# sedsna.net
KiCad netlist of a schematic drawn in Altium Designer
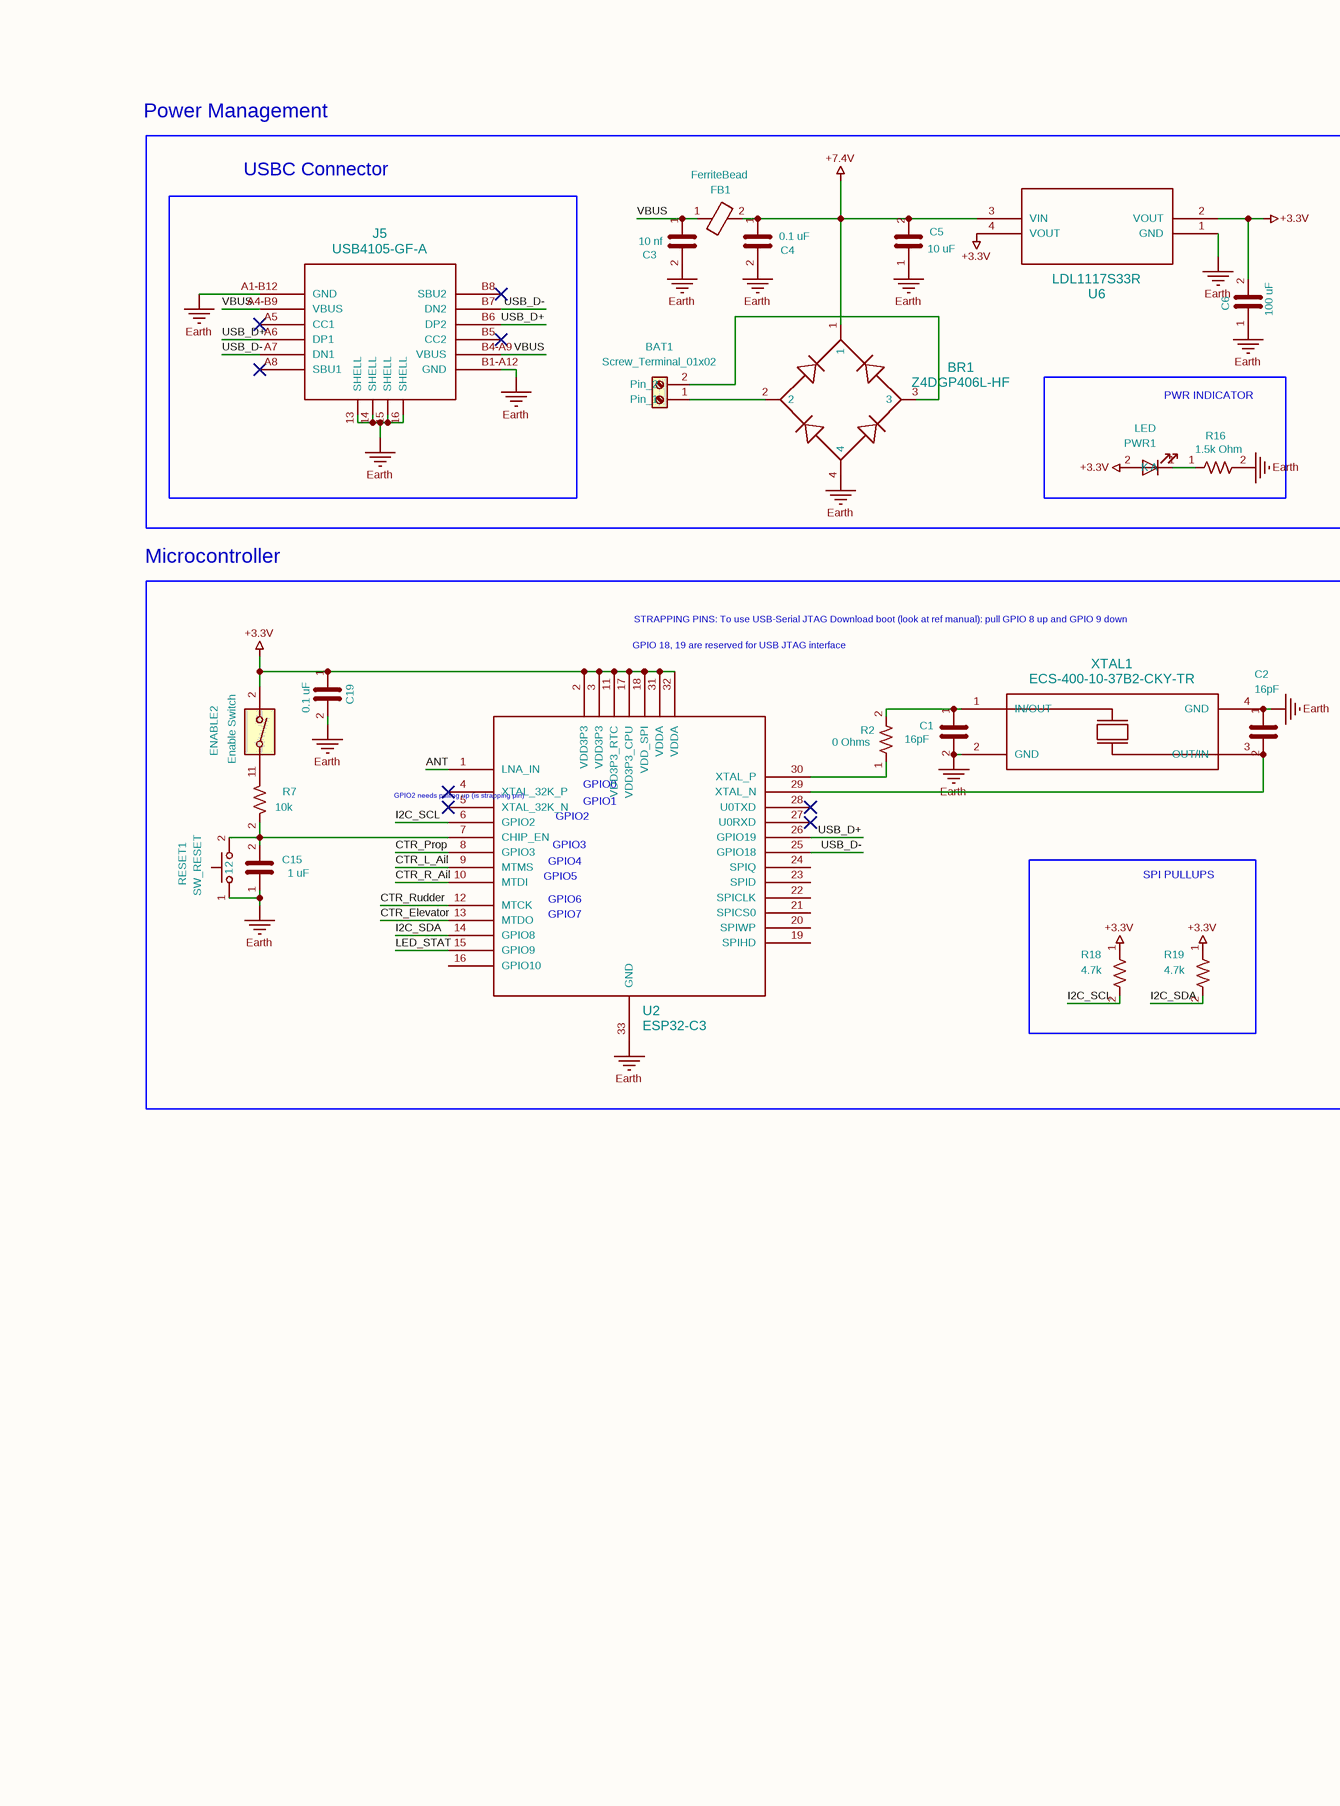
[diagram p0: sedsna.SchDoc, left]
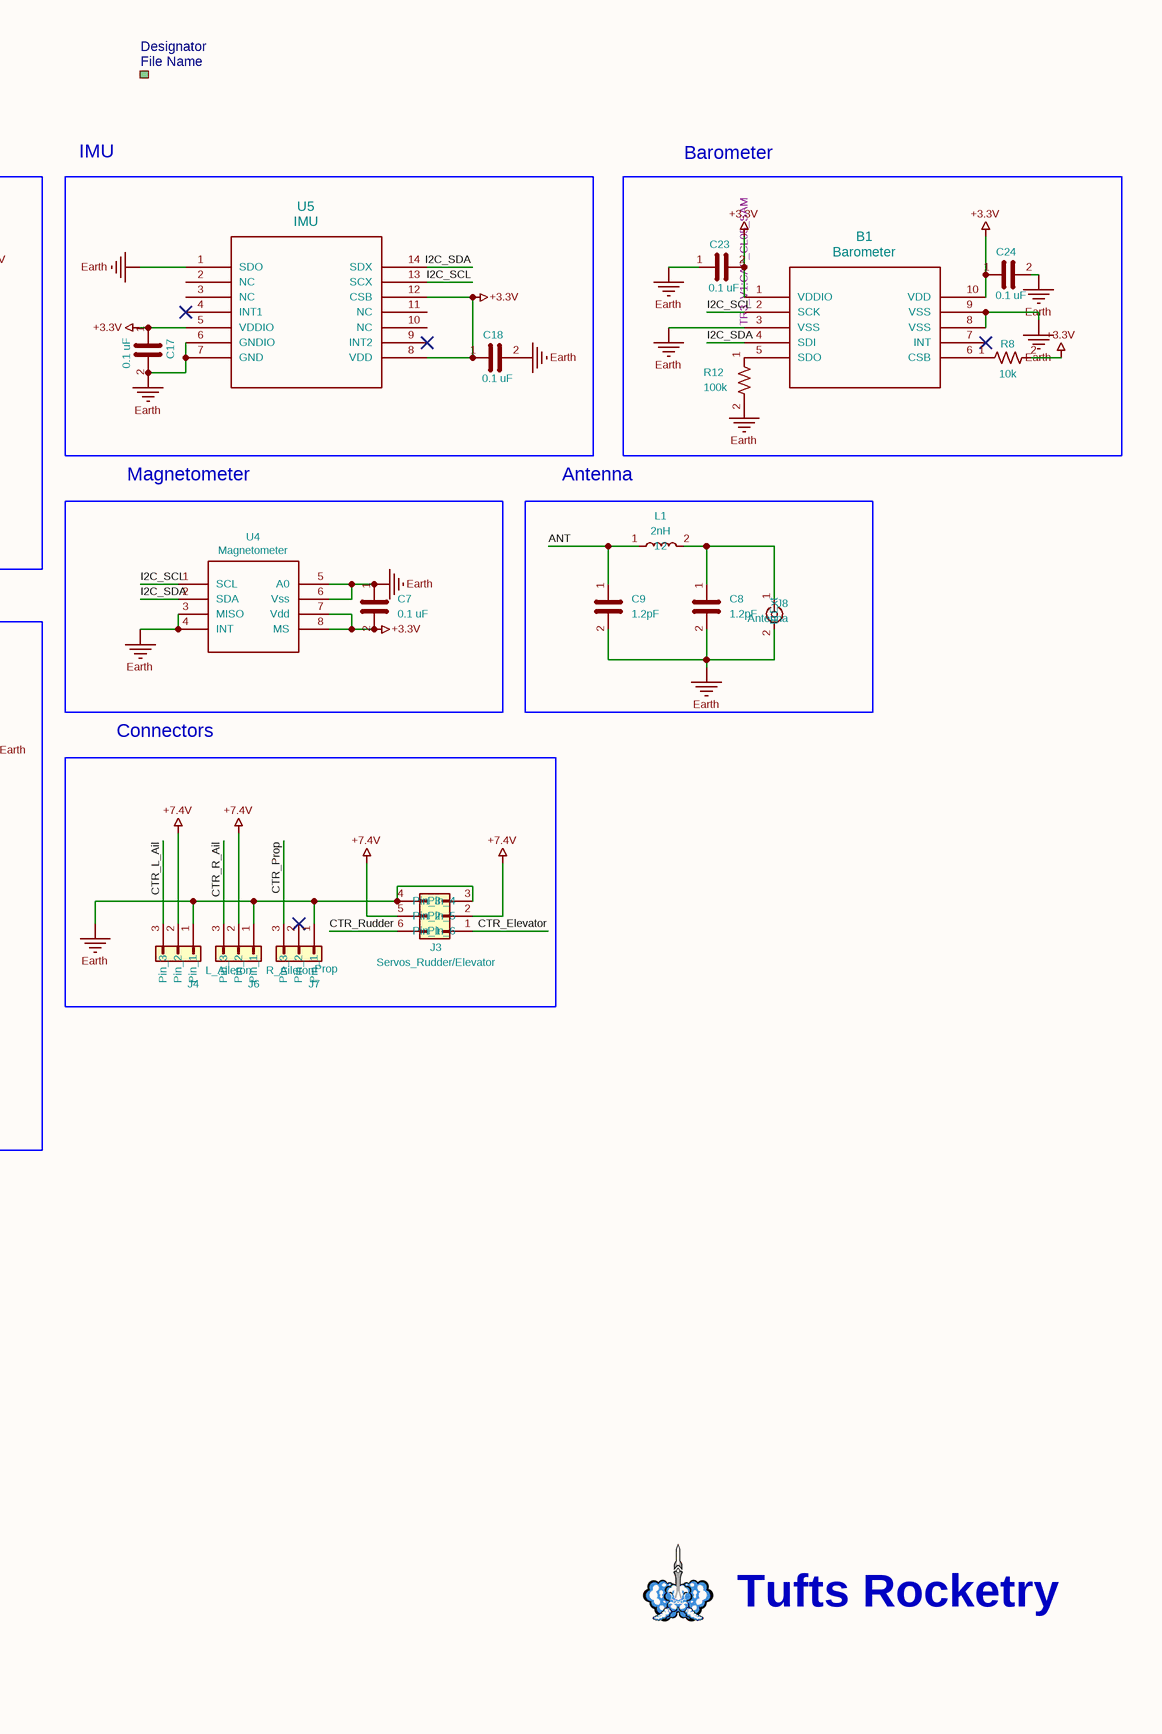
[diagram p1: sedsna.SchDoc, right]

(export (version "E")
  (design (tool "Eeschema 10.0.6"))
  (components
    (comp (ref "B1")
      (value "Barometer")
      (footprint "QFN10_BMP581_BOS")
      (libsource (lib "TR3_V1") (part "BMP581"))
    )
    (comp (ref "BAT1")
      (value "Screw_Terminal_01x02")
      (footprint "TerminalBlock_bornier-2_P5.08mm")
      (libsource (lib "TR3_V1") (part "Screw_Terminal_01x02"))
    )
    (comp (ref "BR1")
      (value "Z4DGP406L-HF")
      (footprint "Z4DGP406L-HF_footprint_N")
      (libsource (lib "TR3_V1") (part "Z4DGP406L-HF"))
    )
    (comp (ref "C1") (value "16pF") (libsource (lib "Device") (part "C")))
    (comp (ref "C2") (value "16pF") (libsource (lib "Device") (part "C")))
    (comp (ref "C3") (value "10 nf") (footprint "C_0603_1608Metric") (libsource (lib "TR3_V1") (part "C")))
    (comp (ref "C4") (value "0.1 uF") (footprint "CAP_CL05_SAM") (libsource (lib "TR3_V1") (part "C")))
    (comp (ref "C5") (value "10 uF") (footprint "C_0805_2012Metric") (libsource (lib "TR3_V1") (part "C")))
    (comp (ref "C6") (value "100 uF") (footprint "C_1206_3216Metric") (libsource (lib "TR3_V1") (part "C")))
    (comp (ref "C7") (value "0.1 uF") (libsource (lib "Device") (part "C")))
    (comp (ref "C8") (value "1.2pF") (libsource (lib "Device") (part "C")))
    (comp (ref "C9") (value "1.2pF") (libsource (lib "Device") (part "C")))
    (comp (ref "C15") (value "1 uF") (footprint "C_0603_1608Metric") (libsource (lib "TR3_V1") (part "C")))
    (comp (ref "C17") (value "0.1 uF") (footprint "CAP_CL05_SAM") (libsource (lib "TR3_V1") (part "C")))
    (comp (ref "C18") (value "0.1 uF") (footprint "CAP_CL05_SAM") (libsource (lib "TR3_V1") (part "C")))
    (comp (ref "C19") (value "0.1 uF") (footprint "CAP_CL05_SAM") (libsource (lib "TR3_V1") (part "C")))
    (comp (ref "C23")
      (value "0.1 uF")
      (footprint "TR3_V1:CAP_CL05_SAM")
      (libsource (lib "TR3_V1") (part "C"))
    )
    (comp (ref "C24") (value "0.1 uF") (footprint "CAP_CL05_SAM") (libsource (lib "TR3_V1") (part "C")))
    (comp (ref "ENABLE2")
      (value "Enable Switch")
      (footprint "SW_DS04-254-2-01BK-SMT")
      (libsource (lib "TR3_V1") (part "SW_DIP_x01"))
    )
    (comp (ref "FB1")
      (value "FerriteBead")
      (footprint "FB_MI0805K400R-10")
      (libsource (lib "Device") (part "FerriteBead"))
    )
    (comp (ref "J3")
      (value "Servos_Rudder/Elevator")
      (libsource (lib "Connector_Generic") (part "Conn_02x03_Counter_Clockwise"))
    )
    (comp (ref "J4") (value "L_Aileron") (libsource (lib "Connector_Generic") (part "Conn_01x03")))
    (comp (ref "J5")
      (value "USB4105-GF-A")
      (footprint "USB4105_GCT")
      (libsource (lib "TR3_V1") (part "USB4105-GF-A"))
    )
    (comp (ref "J6") (value "R_Aileron") (libsource (lib "Connector_Generic") (part "Conn_01x03")))
    (comp (ref "J7") (value "Prop") (libsource (lib "Connector_Generic") (part "Conn_01x03")))
    (comp (ref "J8") (value "Antenna") (libsource (lib "Connector") (part "Conn_Coaxial_Small")))
    (comp (ref "L1") (value "2nH") (libsource (lib "Device") (part "L")))
    (comp (ref "PWR1") (value "LED") (footprint "150080RS75000_WRE") (libsource (lib "TR3_V1") (part "LED")))
    (comp (ref "R2") (value "0 Ohms") (libsource (lib "Device") (part "R_US")))
    (comp (ref "R7")
      (value "10k")
      (footprint "R_0603_1608Metric_Pad0.98x0.95mm_HandSolder")
      (libsource (lib "TR3_V1") (part "R_US"))
    )
    (comp (ref "R8")
      (value "10k")
      (footprint "R_0603_1608Metric_Pad0.98x0.95mm_HandSolder")
      (libsource (lib "TR3_V1") (part "R_US"))
    )
    (comp (ref "R12")
      (value "100k")
      (footprint "R_0603_1608Metric_Pad0.98x0.95mm_HandSolder")
      (libsource (lib "TR3_V1") (part "R_US"))
    )
    (comp (ref "R16")
      (value "1.5k Ohm")
      (footprint "R_0603_1608Metric_Pad0.98x0.95mm_HandSolder")
      (libsource (lib "TR3_V1") (part "R_US"))
    )
    (comp (ref "R18")
      (value "4.7k")
      (footprint "R_0603_1608Metric_Pad0.98x0.95mm_HandSolder")
      (libsource (lib "Device") (part "R_US"))
    )
    (comp (ref "R19")
      (value "4.7k")
      (footprint "R_0603_1608Metric_Pad0.98x0.95mm_HandSolder")
      (libsource (lib "Device") (part "R_US"))
    )
    (comp (ref "RESET1")
      (value "SW_RESET")
      (footprint "2-pronged_THT_button")
      (libsource (lib "TR3_V1") (part "SW_Push"))
    )
    (comp (ref "U2")
      (value "ESP32-C3")
      (footprint "QFN32_5X5_EXP")
      (libsource (lib "sedsna") (part "ESP32-C3"))
    )
    (comp (ref "U4") (value "Magnetometer") (libsource (lib "TR3_V1_from_sun") (part "MAGNETO-MLX90395KDC")))
    (comp (ref "U5") (value "IMU") (footprint "BMI323_BOS") (libsource (lib "TR3_V1") (part "BMI323")))
    (comp (ref "U6")
      (value "LDL1117S33R")
      (footprint "SOT223_STM")
      (libsource (lib "TR3_V1") (part "LDL1117S33R"))
    )
    (comp (ref "XTAL1")
      (value "ECS-400-10-37B2-CKY-TR")
      (footprint "ECX-1637B2_ECS")
      (libsource (lib "TR3_V1") (part "ECS-400-10-37B2-CKY-TR"))
    )
  )
  (nets
    (net (code "1") (name "+3.3V") (class "Default")
      (node (ref "B1") (pin "1") (pinfunction "VDDIO_1") (pintype "passive"))
      (node (ref "B1") (pin "10") (pinfunction "VDD_10") (pintype "passive"))
      (node (ref "C17") (pin "1") (pinfunction "1_1") (pintype "passive"))
      (node (ref "C18") (pin "1") (pinfunction "1_1") (pintype "passive"))
      (node (ref "C19") (pin "1") (pinfunction "1_1") (pintype "passive"))
      (node (ref "C23") (pin "2") (pinfunction "2_2") (pintype "passive"))
      (node (ref "C24") (pin "1") (pinfunction "1_1") (pintype "passive"))
      (node (ref "C6") (pin "2") (pinfunction "2_2") (pintype "passive"))
      (node (ref "C7") (pin "2") (pinfunction "2_2") (pintype "passive"))
      (node (ref "ENABLE2") (pin "2") (pinfunction "2_2") (pintype "passive"))
      (node (ref "PWR1") (pin "2") (pinfunction "A_2") (pintype "passive"))
      (node (ref "R18") (pin "1") (pinfunction "1_1") (pintype "passive"))
      (node (ref "R19") (pin "1") (pinfunction "1_1") (pintype "passive"))
      (node (ref "R8") (pin "2") (pinfunction "2_2") (pintype "passive"))
      (node (ref "U2") (pin "11") (pinfunction "VDD3P3_RTC_11") (pintype "passive"))
      (node (ref "U2") (pin "17") (pinfunction "VDD3P3_CPU_17") (pintype "passive"))
      (node (ref "U2") (pin "18") (pinfunction "VDD_SPI_18") (pintype "passive"))
      (node (ref "U2") (pin "2") (pinfunction "VDD3P3_2") (pintype "passive"))
      (node (ref "U2") (pin "3") (pinfunction "VDD3P3_3") (pintype "passive"))
      (node (ref "U2") (pin "31") (pinfunction "VDDA_31") (pintype "passive"))
      (node (ref "U2") (pin "32") (pinfunction "VDDA_32") (pintype "passive"))
      (node (ref "U4") (pin "7") (pinfunction "Vdd_7") (pintype "passive"))
      (node (ref "U4") (pin "8") (pinfunction "MS_8") (pintype "passive"))
      (node (ref "U5") (pin "12") (pinfunction "CSB_12") (pintype "passive"))
      (node (ref "U5") (pin "5") (pinfunction "VDDIO_5") (pintype "passive"))
      (node (ref "U5") (pin "8") (pinfunction "VDD_8") (pintype "passive"))
      (node (ref "U6") (pin "2") (pinfunction "VOUT_2") (pintype "passive"))
      (node (ref "U6") (pin "4") (pinfunction "VOUT_4") (pintype "passive"))
    )
    (net (code "2") (name "+7.4V") (class "Default")
      (node (ref "BR1") (pin "1") (pinfunction "1_1") (pintype "passive"))
      (node (ref "C4") (pin "1") (pinfunction "1_1") (pintype "passive"))
      (node (ref "C5") (pin "2") (pinfunction "2_2") (pintype "passive"))
      (node (ref "FB1") (pin "2") (pinfunction "2_2") (pintype "passive"))
      (node (ref "J3") (pin "2") (pinfunction "Pin_2_2") (pintype "passive"))
      (node (ref "J3") (pin "5") (pinfunction "Pin_5_5") (pintype "passive"))
      (node (ref "J4") (pin "2") (pinfunction "Pin_2_2") (pintype "passive"))
      (node (ref "J6") (pin "2") (pinfunction "Pin_2_2") (pintype "passive"))
      (node (ref "U6") (pin "3") (pinfunction "VIN_3") (pintype "passive"))
    )
    (net (code "3") (name "/ANT") (class "Default")
      (node (ref "C9") (pin "1") (pinfunction "1_1") (pintype "passive"))
      (node (ref "L1") (pin "1") (pinfunction "1_1") (pintype "passive"))
      (node (ref "U2") (pin "1") (pinfunction "LNA_IN_1") (pintype "passive"))
    )
    (net (code "4") (name "/CTR_Elevator") (class "Default")
      (node (ref "J3") (pin "1") (pinfunction "Pin_1_1") (pintype "passive"))
      (node (ref "U2") (pin "13") (pinfunction "MTDO_13") (pintype "passive"))
    )
    (net (code "5") (name "/CTR_L_Ail") (class "Default")
      (node (ref "J4") (pin "3") (pinfunction "Pin_3_3") (pintype "passive"))
      (node (ref "U2") (pin "9") (pinfunction "MTMS_9") (pintype "passive"))
    )
    (net (code "6") (name "/CTR_Prop") (class "Default")
      (node (ref "J7") (pin "3") (pinfunction "Pin_3_3") (pintype "passive"))
      (node (ref "U2") (pin "8") (pinfunction "GPIO3_8") (pintype "passive"))
    )
    (net (code "7") (name "/CTR_R_Ail") (class "Default")
      (node (ref "J6") (pin "3") (pinfunction "Pin_3_3") (pintype "passive"))
      (node (ref "U2") (pin "10") (pinfunction "MTDI_10") (pintype "passive"))
    )
    (net (code "8") (name "/CTR_Rudder") (class "Default")
      (node (ref "J3") (pin "6") (pinfunction "Pin_6_6") (pintype "passive"))
      (node (ref "U2") (pin "12") (pinfunction "MTCK_12") (pintype "passive"))
    )
    (net (code "9") (name "/I2C_SCL") (class "Default")
      (node (ref "B1") (pin "2") (pinfunction "SCK_2") (pintype "passive"))
      (node (ref "R18") (pin "2") (pinfunction "2_2") (pintype "passive"))
      (node (ref "U2") (pin "6") (pinfunction "GPIO2_6") (pintype "passive"))
      (node (ref "U4") (pin "1") (pinfunction "SCL_1") (pintype "passive"))
      (node (ref "U5") (pin "13") (pinfunction "SCX_13") (pintype "passive"))
    )
    (net (code "10") (name "/I2C_SDA") (class "Default")
      (node (ref "B1") (pin "4") (pinfunction "SDI_4") (pintype "passive"))
      (node (ref "R19") (pin "2") (pinfunction "2_2") (pintype "passive"))
      (node (ref "U2") (pin "14") (pinfunction "GPIO8_14") (pintype "passive"))
      (node (ref "U4") (pin "2") (pinfunction "SDA_2") (pintype "passive"))
      (node (ref "U5") (pin "14") (pinfunction "SDX_14") (pintype "passive"))
    )
    (net (code "11") (name "/LED_STAT") (class "Default")
      (node (ref "U2") (pin "15") (pinfunction "GPIO9_15") (pintype "passive"))
    )
    (net (code "12") (name "/USB_D+") (class "Default")
      (node (ref "J5") (pin "A6") (pinfunction "DP1_A6") (pintype "passive"))
      (node (ref "J5") (pin "B6") (pinfunction "DP2_B6") (pintype "passive"))
      (node (ref "U2") (pin "26") (pinfunction "GPIO19_26") (pintype "passive"))
    )
    (net (code "13") (name "/USB_D-") (class "Default")
      (node (ref "J5") (pin "A7") (pinfunction "DN1_A7") (pintype "passive"))
      (node (ref "J5") (pin "B7") (pinfunction "DN2_B7") (pintype "passive"))
      (node (ref "U2") (pin "25") (pinfunction "GPIO18_25") (pintype "passive"))
    )
    (net (code "14") (name "/VBUS") (class "Default")
      (node (ref "C3") (pin "1") (pinfunction "1_1") (pintype "passive"))
      (node (ref "FB1") (pin "1") (pinfunction "1_1") (pintype "passive"))
      (node (ref "J5") (pin "A4-B9") (pinfunction "VBUS_A4-B9") (pintype "passive"))
      (node (ref "J5") (pin "B4-A9") (pinfunction "VBUS_B4-A9") (pintype "passive"))
    )
    (net (code "15") (name "Earth") (class "Default")
      (node (ref "B1") (pin "3") (pinfunction "VSS_3") (pintype "passive"))
      (node (ref "B1") (pin "8") (pinfunction "VSS_8") (pintype "passive"))
      (node (ref "B1") (pin "9") (pinfunction "VSS_9") (pintype "passive"))
      (node (ref "BR1") (pin "4") (pinfunction "4_4") (pintype "passive"))
      (node (ref "C1") (pin "2") (pinfunction "2_2") (pintype "passive"))
      (node (ref "C15") (pin "1") (pinfunction "1_1") (pintype "passive"))
      (node (ref "C17") (pin "2") (pinfunction "2_2") (pintype "passive"))
      (node (ref "C18") (pin "2") (pinfunction "2_2") (pintype "passive"))
      (node (ref "C19") (pin "2") (pinfunction "2_2") (pintype "passive"))
      (node (ref "C2") (pin "1") (pinfunction "1_1") (pintype "passive"))
      (node (ref "C23") (pin "1") (pinfunction "1_1") (pintype "passive"))
      (node (ref "C24") (pin "2") (pinfunction "2_2") (pintype "passive"))
      (node (ref "C3") (pin "2") (pinfunction "2_2") (pintype "passive"))
      (node (ref "C4") (pin "2") (pinfunction "2_2") (pintype "passive"))
      (node (ref "C5") (pin "1") (pinfunction "1_1") (pintype "passive"))
      (node (ref "C6") (pin "1") (pinfunction "1_1") (pintype "passive"))
      (node (ref "C7") (pin "1") (pinfunction "1_1") (pintype "passive"))
      (node (ref "C8") (pin "2") (pinfunction "2_2") (pintype "passive"))
      (node (ref "C9") (pin "2") (pinfunction "2_2") (pintype "passive"))
      (node (ref "J3") (pin "3") (pinfunction "Pin_3_3") (pintype "passive"))
      (node (ref "J3") (pin "4") (pinfunction "Pin_4_4") (pintype "passive"))
      (node (ref "J4") (pin "1") (pinfunction "Pin_1_1") (pintype "passive"))
      (node (ref "J5") (pin "13") (pinfunction "SHELL_13") (pintype "passive"))
      (node (ref "J5") (pin "14") (pinfunction "SHELL_14") (pintype "passive"))
      (node (ref "J5") (pin "15") (pinfunction "SHELL_15") (pintype "passive"))
      (node (ref "J5") (pin "16") (pinfunction "SHELL_16") (pintype "passive"))
      (node (ref "J5") (pin "A1-B12") (pinfunction "GND_A1-B12") (pintype "passive"))
      (node (ref "J5") (pin "B1-A12") (pinfunction "GND_B1-A12") (pintype "passive"))
      (node (ref "J6") (pin "1") (pinfunction "Pin_1_1") (pintype "passive"))
      (node (ref "J7") (pin "1") (pinfunction "Pin_1_1") (pintype "passive"))
      (node (ref "J8") (pin "2") (pinfunction "Ext_2") (pintype "passive"))
      (node (ref "R12") (pin "2") (pinfunction "2_2") (pintype "passive"))
      (node (ref "R16") (pin "2") (pinfunction "2_2") (pintype "passive"))
      (node (ref "RESET1") (pin "1") (pinfunction "1_1") (pintype "passive"))
      (node (ref "U2") (pin "33") (pinfunction "GND_33") (pintype "passive"))
      (node (ref "U4") (pin "3") (pinfunction "MISO_3") (pintype "passive"))
      (node (ref "U4") (pin "4") (pinfunction "INT_4") (pintype "passive"))
      (node (ref "U4") (pin "5") (pinfunction "A0_5") (pintype "passive"))
      (node (ref "U4") (pin "6") (pinfunction "Vss_6") (pintype "passive"))
      (node (ref "U5") (pin "1") (pinfunction "SDO_1") (pintype "passive"))
      (node (ref "U5") (pin "6") (pinfunction "GNDIO_6") (pintype "passive"))
      (node (ref "U5") (pin "7") (pinfunction "GND_7") (pintype "passive"))
      (node (ref "U6") (pin "1") (pinfunction "GND_1") (pintype "passive"))
      (node (ref "XTAL1") (pin "2") (pinfunction "GND_2") (pintype "passive"))
      (node (ref "XTAL1") (pin "4") (pinfunction "GND_4") (pintype "passive"))
    )
    (net (code "16") (name "Net-(B1-CSB)") (class "Default")
      (node (ref "B1") (pin "6") (pinfunction "CSB_6") (pintype "passive"))
      (node (ref "R8") (pin "1") (pinfunction "1_1") (pintype "passive"))
    )
    (net (code "17") (name "Net-(B1-SDO)") (class "Default")
      (node (ref "B1") (pin "5") (pinfunction "SDO_5") (pintype "passive"))
      (node (ref "R12") (pin "1") (pinfunction "1_1") (pintype "passive"))
    )
    (net (code "18") (name "Net-(BAT1-Pin_1)") (class "Default")
      (node (ref "BAT1") (pin "1") (pinfunction "Pin_1_1") (pintype "passive"))
      (node (ref "BR1") (pin "2") (pinfunction "2_2") (pintype "passive"))
    )
    (net (code "19") (name "Net-(BAT1-Pin_2)") (class "Default")
      (node (ref "BAT1") (pin "2") (pinfunction "Pin_2_2") (pintype "passive"))
      (node (ref "BR1") (pin "3") (pinfunction "3_3") (pintype "passive"))
    )
    (net (code "20") (name "Net-(ENABLE2-Pad1)") (class "Default")
      (node (ref "ENABLE2") (pin "1") (pinfunction "1_1") (pintype "passive"))
      (node (ref "R7") (pin "1") (pinfunction "1_1") (pintype "passive"))
    )
    (net (code "21") (name "Net-(J8-In)") (class "Default")
      (node (ref "C8") (pin "1") (pinfunction "1_1") (pintype "passive"))
      (node (ref "J8") (pin "1") (pinfunction "In_1") (pintype "passive"))
      (node (ref "L1") (pin "2") (pinfunction "2_2") (pintype "passive"))
    )
    (net (code "22") (name "Net-(PWR1-K)") (class "Default")
      (node (ref "PWR1") (pin "1") (pinfunction "K_1") (pintype "passive"))
      (node (ref "R16") (pin "1") (pinfunction "1_1") (pintype "passive"))
    )
    (net (code "23") (name "Net-(U2-CHIP_EN)") (class "Default")
      (node (ref "C15") (pin "2") (pinfunction "2_2") (pintype "passive"))
      (node (ref "R7") (pin "2") (pinfunction "2_2") (pintype "passive"))
      (node (ref "RESET1") (pin "2") (pinfunction "2_2") (pintype "passive"))
      (node (ref "U2") (pin "7") (pinfunction "CHIP_EN_7") (pintype "passive"))
    )
    (net (code "24") (name "Net-(U2-XTAL_N)") (class "Default")
      (node (ref "C2") (pin "2") (pinfunction "2_2") (pintype "passive"))
      (node (ref "U2") (pin "29") (pinfunction "XTAL_N_29") (pintype "passive"))
      (node (ref "XTAL1") (pin "3") (pinfunction "OUT/IN_3") (pintype "passive"))
    )
    (net (code "25") (name "Net-(U2-XTAL_P)") (class "Default")
      (node (ref "R2") (pin "1") (pinfunction "1_1") (pintype "passive"))
      (node (ref "U2") (pin "30") (pinfunction "XTAL_P_30") (pintype "passive"))
    )
    (net (code "26") (name "Net-(XTAL1-IN{slash}OUT)") (class "Default")
      (node (ref "C1") (pin "1") (pinfunction "1_1") (pintype "passive"))
      (node (ref "R2") (pin "2") (pinfunction "2_2") (pintype "passive"))
      (node (ref "XTAL1") (pin "1") (pinfunction "IN/OUT_1") (pintype "passive"))
    )
    (net (code "27") (name "unconnected-(B1-INT-Pad7)") (class "Default")
      (node (ref "B1") (pin "7") (pinfunction "INT_7") (pintype "passive+no_connect"))
    )
    (net (code "28") (name "unconnected-(J5-CC1-PadA5)") (class "Default")
      (node (ref "J5") (pin "A5") (pinfunction "CC1_A5") (pintype "passive+no_connect"))
    )
    (net (code "29") (name "unconnected-(J5-CC2-PadB5)") (class "Default")
      (node (ref "J5") (pin "B5") (pinfunction "CC2_B5") (pintype "passive+no_connect"))
    )
    (net (code "30") (name "unconnected-(J5-SBU1-PadA8)") (class "Default")
      (node (ref "J5") (pin "A8") (pinfunction "SBU1_A8") (pintype "passive+no_connect"))
    )
    (net (code "31") (name "unconnected-(J5-SBU2-PadB8)") (class "Default")
      (node (ref "J5") (pin "B8") (pinfunction "SBU2_B8") (pintype "passive+no_connect"))
    )
    (net (code "32") (name "unconnected-(J7-Pin_2-Pad2)") (class "Default")
      (node (ref "J7") (pin "2") (pinfunction "Pin_2_2") (pintype "passive+no_connect"))
    )
    (net (code "33") (name "unconnected-(U2-GPIO10-Pad16)") (class "Default")
      (node (ref "U2") (pin "16") (pinfunction "GPIO10_16") (pintype "passive"))
    )
    (net (code "34") (name "unconnected-(U2-SPICLK-Pad22)") (class "Default")
      (node (ref "U2") (pin "22") (pinfunction "SPICLK_22") (pintype "passive"))
    )
    (net (code "35") (name "unconnected-(U2-SPICS0-Pad21)") (class "Default")
      (node (ref "U2") (pin "21") (pinfunction "SPICS0_21") (pintype "passive"))
    )
    (net (code "36") (name "unconnected-(U2-SPID-Pad23)") (class "Default")
      (node (ref "U2") (pin "23") (pinfunction "SPID_23") (pintype "passive"))
    )
    (net (code "37") (name "unconnected-(U2-SPIHD-Pad19)") (class "Default")
      (node (ref "U2") (pin "19") (pinfunction "SPIHD_19") (pintype "passive"))
    )
    (net (code "38") (name "unconnected-(U2-SPIQ-Pad24)") (class "Default")
      (node (ref "U2") (pin "24") (pinfunction "SPIQ_24") (pintype "passive"))
    )
    (net (code "39") (name "unconnected-(U2-SPIWP-Pad20)") (class "Default")
      (node (ref "U2") (pin "20") (pinfunction "SPIWP_20") (pintype "passive"))
    )
    (net (code "40") (name "unconnected-(U2-U0RXD-Pad27)") (class "Default")
      (node (ref "U2") (pin "27") (pinfunction "U0RXD_27") (pintype "passive+no_connect"))
    )
    (net (code "41") (name "unconnected-(U2-U0TXD-Pad28)") (class "Default")
      (node (ref "U2") (pin "28") (pinfunction "U0TXD_28") (pintype "passive+no_connect"))
    )
    (net (code "42") (name "unconnected-(U2-XTAL_32K_N-Pad5)") (class "Default")
      (node (ref "U2") (pin "5") (pinfunction "XTAL_32K_N_5") (pintype "passive+no_connect"))
    )
    (net (code "43") (name "unconnected-(U2-XTAL_32K_P-Pad4)") (class "Default")
      (node (ref "U2") (pin "4") (pinfunction "XTAL_32K_P_4") (pintype "passive+no_connect"))
    )
    (net (code "44") (name "unconnected-(U5-INT1-Pad4)") (class "Default")
      (node (ref "U5") (pin "4") (pinfunction "INT1_4") (pintype "passive+no_connect"))
    )
    (net (code "45") (name "unconnected-(U5-INT2-Pad9)") (class "Default")
      (node (ref "U5") (pin "9") (pinfunction "INT2_9") (pintype "passive+no_connect"))
    )
    (net (code "46") (name "unconnected-(U5-NC-Pad2)") (class "Default")
      (node (ref "U5") (pin "2") (pinfunction "NC_2") (pintype "passive"))
    )
    (net (code "47") (name "unconnected-(U5-NC-Pad3)") (class "Default")
      (node (ref "U5") (pin "3") (pinfunction "NC_3") (pintype "passive"))
    )
    (net (code "48") (name "unconnected-(U5-NC-Pad10)") (class "Default")
      (node (ref "U5") (pin "10") (pinfunction "NC_10") (pintype "passive"))
    )
    (net (code "49") (name "unconnected-(U5-NC-Pad11)") (class "Default")
      (node (ref "U5") (pin "11") (pinfunction "NC_11") (pintype "passive"))
    )
  )
)
